# POWER.net
KiCad netlist of a schematic drawn in Altium Designer
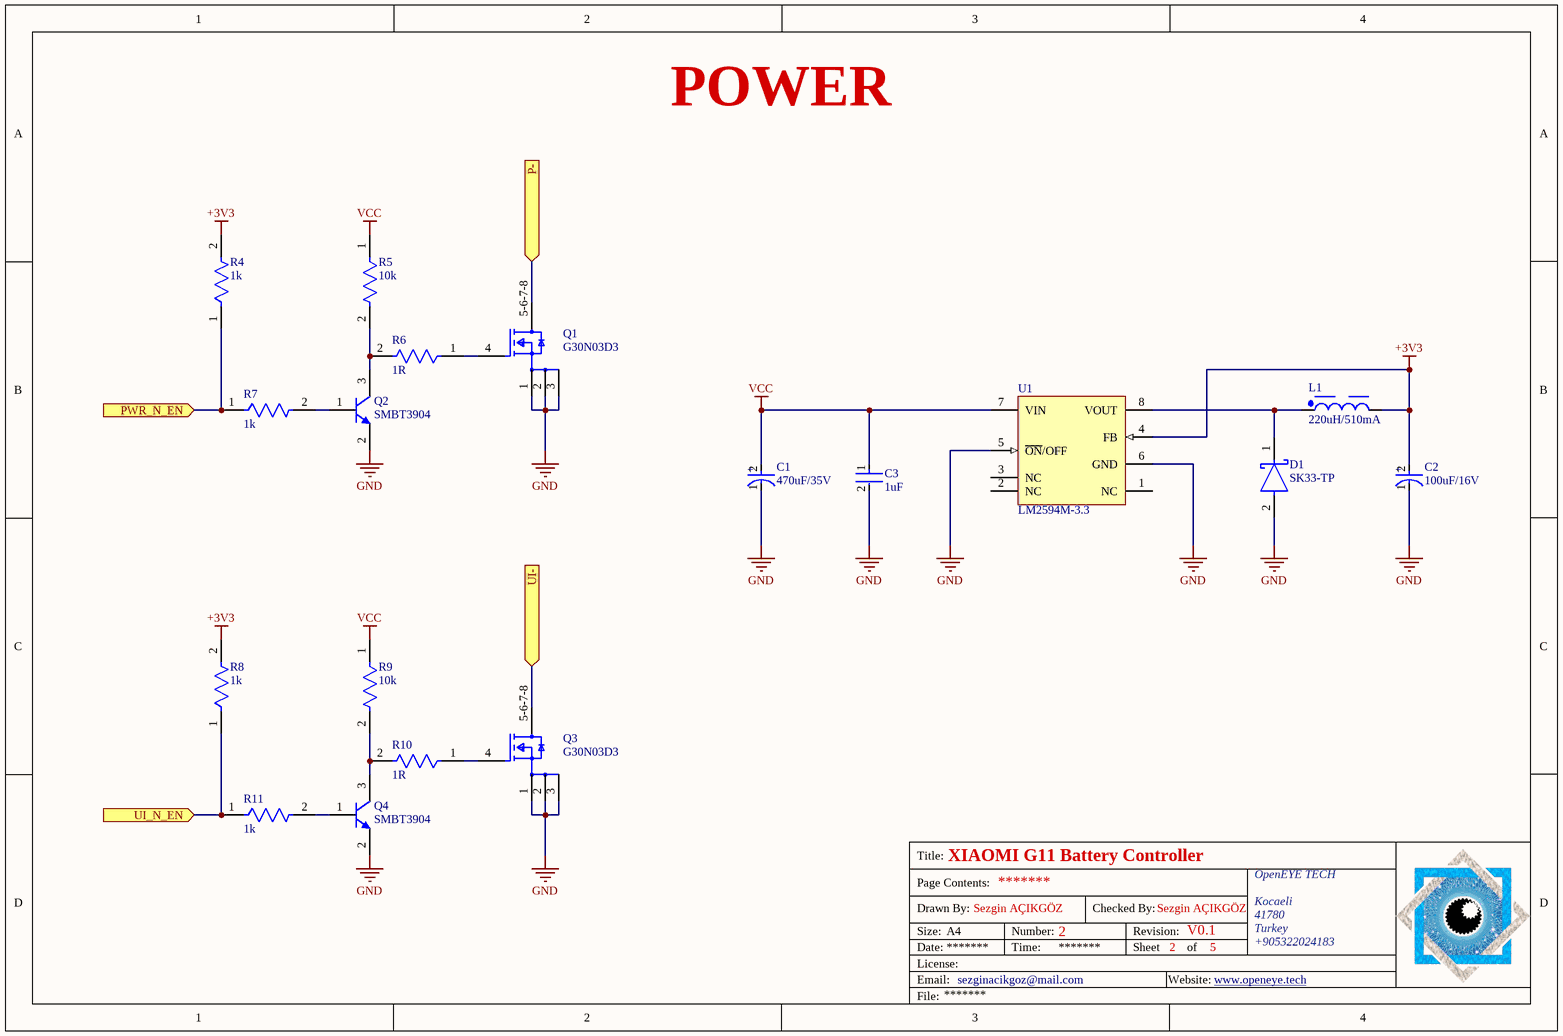
[diagram p0: POWER.SchDoc]

(export (version "E")
  (design (tool "Eeschema 10.0.6"))
  (components
    (comp (ref "C1")
      (value "470uF/35V")
      (footprint "FP-FKSG-MFG")
      (description "CAP ALUM 470UF 20% 35V SMD")
      (fields (field (name "TOLERANCE") "20%") (field (name "LCSC PART #") "C280413"))
      (libsource (lib "Altium Content Vault") (part "a00bbbee19879c290e62620ae7e47b1"))
    )
    (comp (ref "C2")
      (value "100uF/16V")
      (footprint "FP-TAJC-MFG")
      (description "100uF 16V  ±10% 1Ω 2312  SMD Tantalum Capacitor")
      (fields (field (name "TOLERANCE") "10%") (field (name "LCSC PART #") "C122646"))
      (libsource (lib "Altium Content Vault") (part "203bc49f2ac43e59fd269a8c329ed05"))
    )
    (comp (ref "C3")
      (value "1uF")
      (footprint "FP-0603-L_1_6_0_15-W_0_8-IPC_C")
      (description "Ceramic Capacitor General Use 1uF ±10% 50V X7R 0603")
      (fields (field (name "TOLERANCE") "10%") (field (name "LCSC PART #") "C478859"))
      (libsource (lib "Altium Content Vault") (part "11868f565c42a9108669ba33697ecf6"))
    )
    (comp (ref "D1")
      (value "SK33-TP")
      (footprint "FP-SMC-MFG")
      (description "DIODE SCHOTTKY 30V 3A DO214AB")
      (fields (field (name "LCSC PART #") "C151786"))
      (libsource (lib "Altium Content Vault") (part "1d6ec82d83fb6aee721767c19dac4b9"))
    )
    (comp (ref "L1")
      (value "220uH/510mA")
      (footprint "WE-PD2_7850")
      (fields (field (name "LCSC PART #") "C2929444"))
      (libsource (lib "Altium Content Vault") (part "Inductor - 2"))
    )
    (comp (ref "Q1")
      (value "G30N03D3")
      (footprint "FP-511AB-MFG")
      (description "C840054")
      (libsource (lib "Altium Content Vault") (part "7382af88e928fdc71488234cfaaf11c"))
    )
    (comp (ref "Q2")
      (value "SMBT3904")
      (footprint "INF-SOT23_L")
      (description "NPN Silicon Switching Transistor, 40 V VCEO, 200 mA IC, SOT23, Reel, Green")
      (fields (field (name "MANUFACTURER") "Infineon") (field (name "LCSC PART #") "C896900"))
      (libsource (lib "Altium Content Vault") (part "INF-BJTNPN-BEC-3"))
    )
    (comp (ref "Q3")
      (value "G30N03D3")
      (footprint "FP-511AB-MFG")
      (description "C840054")
      (libsource (lib "Altium Content Vault") (part "7382af88e928fdc71488234cfaaf11c"))
    )
    (comp (ref "Q4")
      (value "SMBT3904")
      (footprint "INF-SOT23_L")
      (description "C896900")
      (fields (field (name "MANUFACTURER") "Infineon"))
      (libsource (lib "Altium Content Vault") (part "INF-BJTNPN-BEC-3"))
    )
    (comp (ref "R4")
      (value "1k")
      (footprint "FP-RP731J-MFG")
      (fields
        (field (name "MANUFACTURER") "TE Connectivity")
        (field (name "OCTOPART") "https://octopart.com/rp73d1j8r45btdg-te+connectivity-42630912")
        (field (name "MANUFACTURER PART NUMBER") "RP73D1J8R45BTDG")
      )
      (libsource (lib "Altium Content Vault") (part "1029c3af85768c4190bb7ad29bc67b5"))
    )
    (comp (ref "R5")
      (value "10k")
      (footprint "FP-RP731J-MFG")
      (fields
        (field (name "MANUFACTURER") "TE Connectivity")
        (field (name "OCTOPART") "https://octopart.com/rp73d1j8r45btdg-te+connectivity-42630912")
        (field (name "MANUFACTURER PART NUMBER") "RP73D1J8R45BTDG")
      )
      (libsource (lib "Altium Content Vault") (part "1029c3af85768c4190bb7ad29bc67b5"))
    )
    (comp (ref "R6")
      (value "1R")
      (footprint "FP-RP731J-MFG")
      (fields
        (field (name "MANUFACTURER") "TE Connectivity")
        (field (name "OCTOPART") "https://octopart.com/rp73d1j8r45btdg-te+connectivity-42630912")
        (field (name "MANUFACTURER PART NUMBER") "RP73D1J8R45BTDG")
      )
      (libsource (lib "Altium Content Vault") (part "1029c3af85768c4190bb7ad29bc67b5"))
    )
    (comp (ref "R7")
      (value "1k")
      (footprint "FP-RP731J-MFG")
      (fields
        (field (name "MANUFACTURER") "TE Connectivity")
        (field (name "OCTOPART") "https://octopart.com/rp73d1j8r45btdg-te+connectivity-42630912")
        (field (name "MANUFACTURER PART NUMBER") "RP73D1J8R45BTDG")
      )
      (libsource (lib "Altium Content Vault") (part "1029c3af85768c4190bb7ad29bc67b5"))
    )
    (comp (ref "R8")
      (value "1k")
      (footprint "FP-RP731J-MFG")
      (fields
        (field (name "MANUFACTURER") "TE Connectivity")
        (field (name "OCTOPART") "https://octopart.com/rp73d1j8r45btdg-te+connectivity-42630912")
        (field (name "MANUFACTURER PART NUMBER") "RP73D1J8R45BTDG")
      )
      (libsource (lib "Altium Content Vault") (part "1029c3af85768c4190bb7ad29bc67b5"))
    )
    (comp (ref "R9")
      (value "10k")
      (footprint "FP-RP731J-MFG")
      (fields
        (field (name "MANUFACTURER") "TE Connectivity")
        (field (name "OCTOPART") "https://octopart.com/rp73d1j8r45btdg-te+connectivity-42630912")
        (field (name "MANUFACTURER PART NUMBER") "RP73D1J8R45BTDG")
      )
      (libsource (lib "Altium Content Vault") (part "1029c3af85768c4190bb7ad29bc67b5"))
    )
    (comp (ref "R10")
      (value "1R")
      (footprint "FP-RP731J-MFG")
      (fields
        (field (name "MANUFACTURER") "TE Connectivity")
        (field (name "OCTOPART") "https://octopart.com/rp73d1j8r45btdg-te+connectivity-42630912")
        (field (name "MANUFACTURER PART NUMBER") "RP73D1J8R45BTDG")
      )
      (libsource (lib "Altium Content Vault") (part "1029c3af85768c4190bb7ad29bc67b5"))
    )
    (comp (ref "R11")
      (value "1k")
      (footprint "FP-RP731J-MFG")
      (fields
        (field (name "MANUFACTURER") "TE Connectivity")
        (field (name "OCTOPART") "https://octopart.com/rp73d1j8r45btdg-te+connectivity-42630912")
        (field (name "MANUFACTURER PART NUMBER") "RP73D1J8R45BTDG")
      )
      (libsource (lib "Altium Content Vault") (part "1029c3af85768c4190bb7ad29bc67b5"))
    )
    (comp (ref "U1")
      (value "LM2594M-3.3")
      (footprint "D0008A_M")
      (description "SIMPLE SWITCHER® Power Converter 150 KHz 0.5A Step-Down Voltage Regulator, 8-pin Narrow SOIC")
      (fields (field (name "MANUFACTURER") "Texas Instruments") (field (name "LCSC PART #") "C3029048"))
      (libsource (lib "Altium Content Vault") (part "PM-REG-LM2594M"))
    )
  )
  (nets
    (net (code "1") (name "+3V3") (class "Default")
      (node (ref "C2") (pin "2") (pinfunction "A_2") (pintype "passive"))
      (node (ref "L1") (pin "2") (pinfunction "2_2") (pintype "passive"))
      (node (ref "R4") (pin "2") (pinfunction "2_2") (pintype "passive"))
      (node (ref "R8") (pin "2") (pinfunction "2_2") (pintype "passive"))
      (node (ref "U1") (pin "4") (pinfunction "FB_4") (pintype "input"))
    )
    (net (code "2") (name "/P-") (class "Default")
      (node (ref "Q1") (pin "5-6-7-8") (pinfunction "D_5-6-7-8") (pintype "passive"))
    )
    (net (code "3") (name "/PWR_N_EN") (class "Default")
      (node (ref "R4") (pin "1") (pinfunction "1_1") (pintype "passive"))
      (node (ref "R7") (pin "1") (pinfunction "1_1") (pintype "passive"))
    )
    (net (code "4") (name "/UI-") (class "Default")
      (node (ref "Q3") (pin "5-6-7-8") (pinfunction "D_5-6-7-8") (pintype "passive"))
    )
    (net (code "5") (name "/UI_N_EN") (class "Default")
      (node (ref "R11") (pin "1") (pinfunction "1_1") (pintype "passive"))
      (node (ref "R8") (pin "1") (pinfunction "1_1") (pintype "passive"))
    )
    (net (code "6") (name "GND") (class "Default")
      (node (ref "C1") (pin "1") (pinfunction "C_1") (pintype "passive"))
      (node (ref "C2") (pin "1") (pinfunction "C_1") (pintype "passive"))
      (node (ref "C3") (pin "2") (pinfunction "2_2") (pintype "passive"))
      (node (ref "D1") (pin "2") (pinfunction "A_2") (pintype "passive"))
      (node (ref "Q1") (pin "1") (pinfunction "S_1") (pintype "passive"))
      (node (ref "Q1") (pin "2") (pinfunction "S_2") (pintype "passive"))
      (node (ref "Q1") (pin "3") (pinfunction "S_3") (pintype "passive"))
      (node (ref "Q2") (pin "2") (pinfunction "E_2") (pintype "passive"))
      (node (ref "Q3") (pin "1") (pinfunction "S_1") (pintype "passive"))
      (node (ref "Q3") (pin "2") (pinfunction "S_2") (pintype "passive"))
      (node (ref "Q3") (pin "3") (pinfunction "S_3") (pintype "passive"))
      (node (ref "Q4") (pin "2") (pinfunction "E_2") (pintype "passive"))
      (node (ref "U1") (pin "5") (pinfunction "~{ON}/OFF_5") (pintype "input"))
      (node (ref "U1") (pin "6") (pinfunction "GND_6") (pintype "power_in"))
    )
    (net (code "7") (name "Net-(D1-C)") (class "Default")
      (node (ref "D1") (pin "1") (pinfunction "C_1") (pintype "passive"))
      (node (ref "L1") (pin "1") (pinfunction "1_1") (pintype "passive"))
      (node (ref "U1") (pin "8") (pinfunction "VOUT_8") (pintype "power_in"))
    )
    (net (code "8") (name "Net-(Q1-G)") (class "Default")
      (node (ref "Q1") (pin "4") (pinfunction "G_4") (pintype "passive"))
      (node (ref "R6") (pin "1") (pinfunction "1_1") (pintype "passive"))
    )
    (net (code "9") (name "Net-(Q2-B)") (class "Default")
      (node (ref "Q2") (pin "1") (pinfunction "B_1") (pintype "passive"))
      (node (ref "R7") (pin "2") (pinfunction "2_2") (pintype "passive"))
    )
    (net (code "10") (name "Net-(Q2-C)") (class "Default")
      (node (ref "Q2") (pin "3") (pinfunction "C_3") (pintype "passive"))
      (node (ref "R5") (pin "2") (pinfunction "2_2") (pintype "passive"))
      (node (ref "R6") (pin "2") (pinfunction "2_2") (pintype "passive"))
    )
    (net (code "11") (name "Net-(Q3-G)") (class "Default")
      (node (ref "Q3") (pin "4") (pinfunction "G_4") (pintype "passive"))
      (node (ref "R10") (pin "1") (pinfunction "1_1") (pintype "passive"))
    )
    (net (code "12") (name "Net-(Q4-B)") (class "Default")
      (node (ref "Q4") (pin "1") (pinfunction "B_1") (pintype "passive"))
      (node (ref "R11") (pin "2") (pinfunction "2_2") (pintype "passive"))
    )
    (net (code "13") (name "Net-(Q4-C)") (class "Default")
      (node (ref "Q4") (pin "3") (pinfunction "C_3") (pintype "passive"))
      (node (ref "R10") (pin "2") (pinfunction "2_2") (pintype "passive"))
      (node (ref "R9") (pin "2") (pinfunction "2_2") (pintype "passive"))
    )
    (net (code "14") (name "VCC") (class "Default")
      (node (ref "C1") (pin "2") (pinfunction "A_2") (pintype "passive"))
      (node (ref "C3") (pin "1") (pinfunction "1_1") (pintype "passive"))
      (node (ref "R5") (pin "1") (pinfunction "1_1") (pintype "passive"))
      (node (ref "R9") (pin "1") (pinfunction "1_1") (pintype "passive"))
      (node (ref "U1") (pin "7") (pinfunction "VIN_7") (pintype "power_in"))
    )
    (net (code "15") (name "unconnected-(U1-NC-Pad1)") (class "Default")
      (node (ref "U1") (pin "1") (pinfunction "NC_1") (pintype "passive"))
    )
    (net (code "16") (name "unconnected-(U1-NC-Pad2)") (class "Default")
      (node (ref "U1") (pin "2") (pinfunction "NC_2") (pintype "passive"))
    )
    (net (code "17") (name "unconnected-(U1-NC-Pad3)") (class "Default")
      (node (ref "U1") (pin "3") (pinfunction "NC_3") (pintype "passive"))
    )
  )
)
